# SensorSheet.net
KiCad netlist of a schematic drawn in Altium Designer
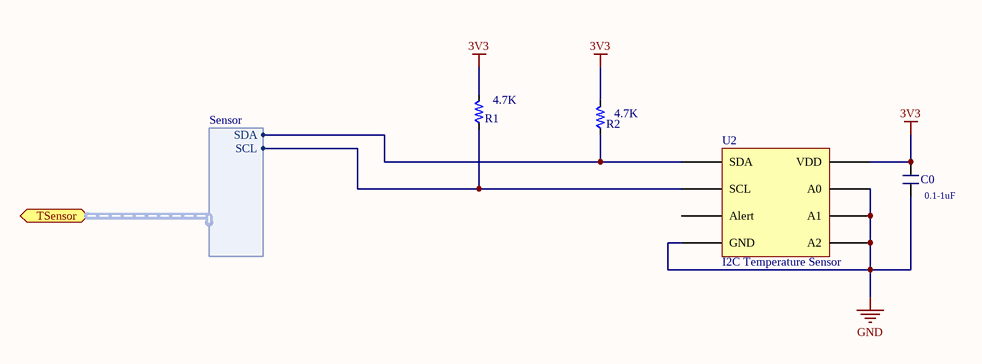
[diagram p0: SensorSheet.SchDoc]

(export (version "E")
  (design (tool "Eeschema 10.0.6"))
  (components
    (comp (ref "C0")
      (value "SCH_GENERIC_CAPACITOR_0603")
      (footprint "PCB_GENERIC_SMD_0603")
      (description "Generic SMD capacitor 0603")
      (fields (field (name "TOLERANCE") "*%") (field (name "CAPACITANCE") "0.1-1uF"))
      (libsource (lib "Generic 0603 Capacitor") (part "SCH_GENERIC_CAPACITOR_0603"))
    )
    (comp (ref "R1")
      (value "SCH_GENERIC_RESISTOR_0603")
      (footprint "PCB_GENERIC_SMD_0603")
      (description "Generic SMD resistor 0603")
      (fields (field (name "RESISTANCE") "4.7K"))
      (libsource (lib "Generic 0603 Resistor") (part "SCH_GENERIC_RESISTOR_0603"))
    )
    (comp (ref "R2")
      (value "SCH_GENERIC_RESISTOR_0603")
      (footprint "PCB_GENERIC_SMD_0603")
      (description "Generic SMD resistor 0603")
      (fields (field (name "RESISTANCE") "4.7K"))
      (libsource (lib "Generic 0603 Resistor") (part "SCH_GENERIC_RESISTOR_0603"))
    )
    (comp (ref "U2")
      (value "I2C Temperature Sensor")
      (footprint "SENSOR TEMP I2C/SMBUS 8MSOP")
      (libsource (lib "Microchip I2C Temperature Sensor") (part "Temperature Sensor Digital, Local -40°C ~ 125°C 10 b 8-MSOP, Digikey; MCP9808T-E/MSCT-ND Mfg; MCP9808T-E/MS"))
    )
  )
  (nets
    (net (code "3") (name "3V3") (class "Default")
      (node (ref "C0") (pin "2") (pinfunction "2_2") (pintype "passive"))
      (node (ref "R1") (pin "2") (pinfunction "2_2") (pintype "passive"))
      (node (ref "R2") (pin "2") (pinfunction "2_2") (pintype "passive"))
      (node (ref "U2") (pin "8") (pinfunction "VDD_8") (pintype "passive"))
    )
    (net (code "4") (name "GND") (class "Default")
      (node (ref "C0") (pin "1") (pinfunction "1_1") (pintype "passive"))
      (node (ref "U2") (pin "4") (pinfunction "GND_4") (pintype "passive"))
      (node (ref "U2") (pin "5") (pinfunction "A2_5") (pintype "passive"))
      (node (ref "U2") (pin "6") (pinfunction "A1_6") (pintype "passive"))
      (node (ref "U2") (pin "7") (pinfunction "A0_7") (pintype "passive"))
    )
    (net (code "5") (name "Net-(U2-SCL)") (class "Default")
      (node (ref "R1") (pin "1") (pinfunction "1_1") (pintype "passive"))
      (node (ref "U2") (pin "2") (pinfunction "SCL_2") (pintype "passive"))
    )
    (net (code "6") (name "Net-(U2-SDA)") (class "Default")
      (node (ref "R2") (pin "1") (pinfunction "1_1") (pintype "passive"))
      (node (ref "U2") (pin "1") (pinfunction "SDA_1") (pintype "passive"))
    )
    (net (code "7") (name "unconnected-(U2-Alert-Pad3)") (class "Default")
      (node (ref "U2") (pin "3") (pinfunction "Alert_3") (pintype "passive"))
    )
  )
)
